# Interface_Accelerometer_2.net
KiCad netlist of a schematic drawn in Altium Designer
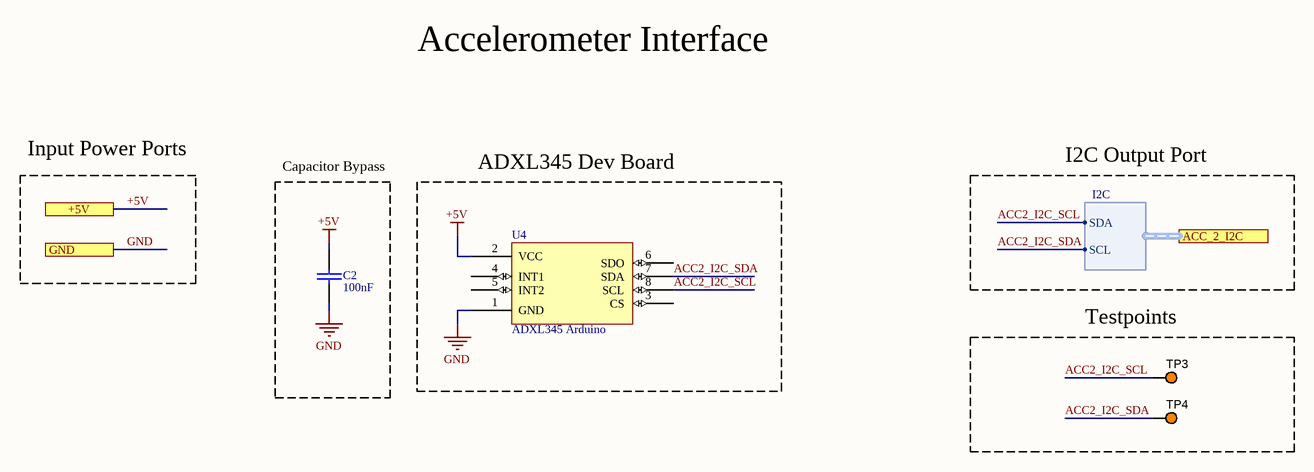
[diagram p0: Interface_Accelerometer_2.SchDoc]

(export (version "E")
  (design (tool "Eeschema 10.0.6"))
  (components
    (comp (ref "C2") (value "100nF") (footprint "CAP200") (libsource (lib "LIBEBAL") (part "CAP")))
    (comp (ref "TP3")
      (value "5003")
      (footprint "KSTN-5003")
      (description "Test Point, Orange, Height 4.6 mm, Tail Length 3 mm, 1-Pin THD, RoHS")
      (fields (field (name "MANUFACTURER") "Keystone"))
      (libsource (lib "TD") (part "TESTPOINT_ORANGE"))
    )
    (comp (ref "TP4")
      (value "5003")
      (footprint "KSTN-5003")
      (description "Test Point, Orange, Height 4.6 mm, Tail Length 3 mm, 1-Pin THD, RoHS")
      (fields (field (name "MANUFACTURER") "Keystone"))
      (libsource (lib "TD") (part "TESTPOINT_ORANGE"))
    )
    (comp (ref "U4")
      (value "ADXL345 Arduino")
      (footprint "GY-521 MPU6050")
      (libsource (lib "SiProFaSi") (part "ADXL345 Arduino"))
    )
  )
  (nets
    (net (code "2") (name "+5V") (class "Default")
      (node (ref "C2") (pin "1") (pinfunction "1_1") (pintype "passive"))
      (node (ref "U4") (pin "2") (pinfunction "VCC_2") (pintype "power_in"))
    )
    (net (code "3") (name "/ACC2_I2C_SCL") (class "Default")
      (node (ref "TP3") (pin "1") (pinfunction "1_1") (pintype "passive"))
      (node (ref "U4") (pin "8") (pinfunction "SCL_8") (pintype "bidirectional"))
    )
    (net (code "4") (name "/ACC2_I2C_SDA") (class "Default")
      (node (ref "TP4") (pin "1") (pinfunction "1_1") (pintype "passive"))
      (node (ref "U4") (pin "7") (pinfunction "SDA_7") (pintype "bidirectional"))
    )
    (net (code "6") (name "GND") (class "Default")
      (node (ref "C2") (pin "2") (pinfunction "2_2") (pintype "passive"))
      (node (ref "U4") (pin "1") (pinfunction "GND_1") (pintype "passive"))
    )
    (net (code "7") (name "unconnected-(U4-CS-Pad3)") (class "Default")
      (node (ref "U4") (pin "3") (pinfunction "CS_3") (pintype "bidirectional"))
    )
    (net (code "8") (name "unconnected-(U4-INT1-Pad4)") (class "Default")
      (node (ref "U4") (pin "4") (pinfunction "INT1_4") (pintype "bidirectional"))
    )
    (net (code "9") (name "unconnected-(U4-INT2-Pad5)") (class "Default")
      (node (ref "U4") (pin "5") (pinfunction "INT2_5") (pintype "bidirectional"))
    )
    (net (code "10") (name "unconnected-(U4-SDO-Pad6)") (class "Default")
      (node (ref "U4") (pin "6") (pinfunction "SDO_6") (pintype "bidirectional"))
    )
  )
)
